# Control.net
KiCad netlist of a schematic drawn in Altium Designer
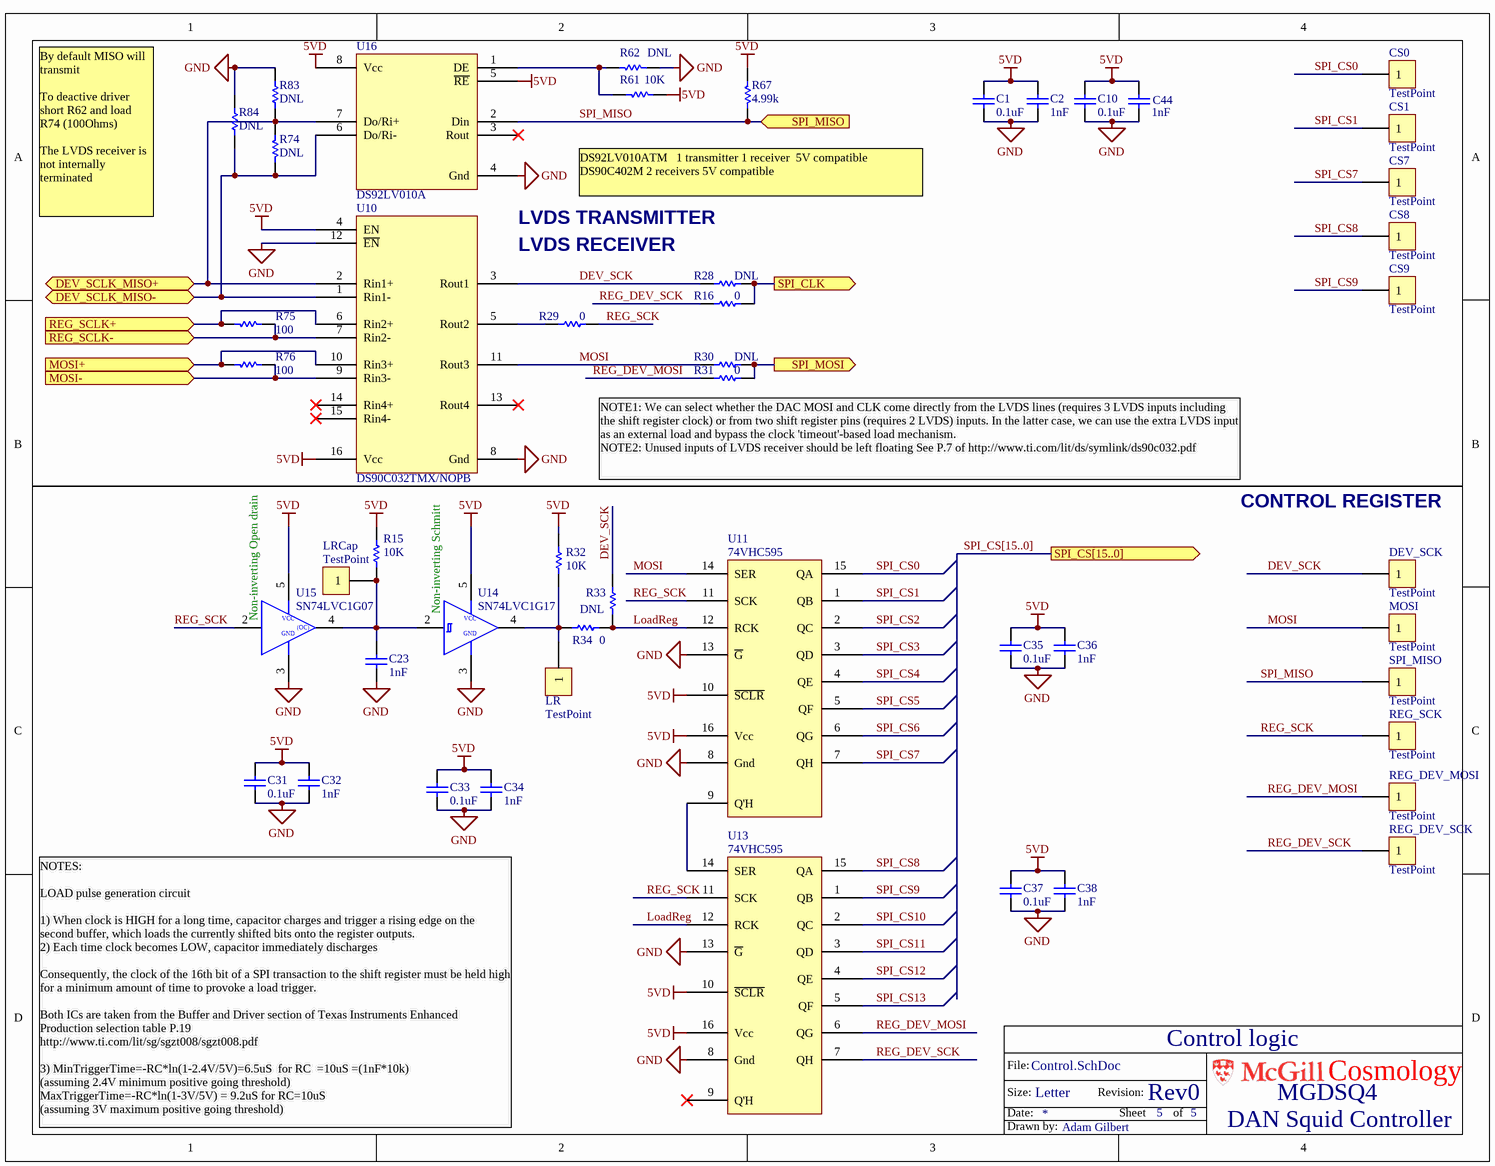
[diagram p0: Control.SchDoc]

(export (version "E")
  (design (tool "Eeschema 10.0.6"))
  (components
    (comp (ref "C1")
      (value "0.1uF")
      (footprint "0603")
      (description "Capacitor, Ceramic, 0603")
      (fields (field (name "MANUFACTURER") "Generic"))
      (libsource (lib "MiniSquidCtrl") (part "Cap0603"))
    )
    (comp (ref "C2")
      (value "1nF")
      (footprint "0603")
      (description "Capacitor, Ceramic, 0603")
      (fields (field (name "MANUFACTURER") "Generic"))
      (libsource (lib "MiniSquidCtrl") (part "Cap0603"))
    )
    (comp (ref "C10")
      (value "0.1uF")
      (footprint "0603")
      (description "Capacitor, Ceramic, 0603")
      (fields (field (name "MANUFACTURER") "Generic"))
      (libsource (lib "MiniSquidCtrl") (part "Cap0603"))
    )
    (comp (ref "C23")
      (value "1nF")
      (footprint "0603")
      (description "Capacitor, Ceramic, 0603")
      (fields (field (name "MANUFACTURER") "Generic"))
      (libsource (lib "MiniSquidCtrl") (part "Cap0603"))
    )
    (comp (ref "C31")
      (value "0.1uF")
      (footprint "0603")
      (description "Capacitor, Ceramic, 0603")
      (fields (field (name "MANUFACTURER") "Generic"))
      (libsource (lib "MiniSquidCtrl") (part "Cap0603"))
    )
    (comp (ref "C32")
      (value "1nF")
      (footprint "0603")
      (description "Capacitor, Ceramic, 0603")
      (fields (field (name "MANUFACTURER") "Generic"))
      (libsource (lib "MiniSquidCtrl") (part "Cap0603"))
    )
    (comp (ref "C33")
      (value "0.1uF")
      (footprint "0603")
      (description "Capacitor, Ceramic, 0603")
      (fields (field (name "MANUFACTURER") "Generic"))
      (libsource (lib "MiniSquidCtrl") (part "Cap0603"))
    )
    (comp (ref "C34")
      (value "1nF")
      (footprint "0603")
      (description "Capacitor, Ceramic, 0603")
      (fields (field (name "MANUFACTURER") "Generic"))
      (libsource (lib "MiniSquidCtrl") (part "Cap0603"))
    )
    (comp (ref "C35")
      (value "0.1uF")
      (footprint "0603")
      (description "Capacitor, Ceramic, 0603")
      (fields (field (name "MANUFACTURER") "Generic"))
      (libsource (lib "MiniSquidCtrl") (part "Cap0603"))
    )
    (comp (ref "C36")
      (value "1nF")
      (footprint "0603")
      (description "Capacitor, Ceramic, 0603")
      (fields (field (name "MANUFACTURER") "Generic"))
      (libsource (lib "MiniSquidCtrl") (part "Cap0603"))
    )
    (comp (ref "C37")
      (value "0.1uF")
      (footprint "0603")
      (description "Capacitor, Ceramic, 0603")
      (fields (field (name "MANUFACTURER") "Generic"))
      (libsource (lib "MiniSquidCtrl") (part "Cap0603"))
    )
    (comp (ref "C38")
      (value "1nF")
      (footprint "0603")
      (description "Capacitor, Ceramic, 0603")
      (fields (field (name "MANUFACTURER") "Generic"))
      (libsource (lib "MiniSquidCtrl") (part "Cap0603"))
    )
    (comp (ref "C44")
      (value "1nF")
      (footprint "0603")
      (description "Capacitor, Ceramic, 0603")
      (fields (field (name "MANUFACTURER") "Generic"))
      (libsource (lib "MiniSquidCtrl") (part "Cap0603"))
    )
    (comp (ref "CS0")
      (value "TestPoint")
      (footprint "TP-3520-SK")
      (description "TestPoint1")
      (libsource (lib "MiniSquidCtrl") (part "TestPoint"))
    )
    (comp (ref "CS1")
      (value "TestPoint")
      (footprint "TP-3520-SK")
      (description "TestPoint1")
      (libsource (lib "MiniSquidCtrl") (part "TestPoint"))
    )
    (comp (ref "CS7")
      (value "TestPoint")
      (footprint "TP-3520-SK")
      (description "TestPoint1")
      (libsource (lib "MiniSquidCtrl") (part "TestPoint"))
    )
    (comp (ref "CS8")
      (value "TestPoint")
      (footprint "TP-3520-SK")
      (description "TestPoint1")
      (libsource (lib "MiniSquidCtrl") (part "TestPoint"))
    )
    (comp (ref "CS9")
      (value "TestPoint")
      (footprint "TP-3520-SK")
      (description "TestPoint1")
      (libsource (lib "MiniSquidCtrl") (part "TestPoint"))
    )
    (comp (ref "DEV_SCK")
      (value "TestPoint")
      (footprint "TP-3520-SK")
      (description "TestPoint1")
      (libsource (lib "MiniSquidCtrl") (part "TestPoint"))
    )
    (comp (ref "LR")
      (value "TestPoint")
      (footprint "TP-3520-SK")
      (description "TestPoint1")
      (libsource (lib "") (part "TestPoint_2"))
    )
    (comp (ref "LRCap")
      (value "TestPoint")
      (footprint "TP-3520-SK")
      (description "TestPoint1")
      (libsource (lib "") (part "TestPoint_1"))
    )
    (comp (ref "MOSI")
      (value "TestPoint")
      (footprint "TP-3520-SK")
      (description "TestPoint1")
      (libsource (lib "MiniSquidCtrl") (part "TestPoint"))
    )
    (comp (ref "R15")
      (value "10K")
      (footprint "0603")
      (description "RES 0603")
      (fields (field (name "MANUFACTURER") "Generic") (field (name "Comment") "10k"))
      (libsource (lib "MiniSquidCtrl") (part "RES 0603"))
    )
    (comp (ref "R16")
      (value "0")
      (footprint "0603")
      (description "RES 0603")
      (fields (field (name "MANUFACTURER") "Generic"))
      (libsource (lib "MiniSquidCtrl") (part "RES 0603"))
    )
    (comp (ref "R28")
      (value "DNL")
      (footprint "0603")
      (description "Resistor")
      (fields (field (name "TOLERANCE") "1%") (field (name "POWER") "1/10W"))
      (libsource (lib "MiniSquidCtrl") (part "RES 0603"))
    )
    (comp (ref "R29")
      (value "0")
      (footprint "0603")
      (description "RES 0603")
      (fields (field (name "MANUFACTURER") "Generic"))
      (libsource (lib "MiniSquidCtrl") (part "RES 0603"))
    )
    (comp (ref "R30")
      (value "DNL")
      (footprint "0603")
      (description "Resistor")
      (fields (field (name "TOLERANCE") "1%") (field (name "POWER") "1/10W"))
      (libsource (lib "MiniSquidCtrl") (part "RES 0603"))
    )
    (comp (ref "R31")
      (value "0")
      (footprint "0603")
      (description "RES 0603")
      (fields (field (name "MANUFACTURER") "Generic"))
      (libsource (lib "MiniSquidCtrl") (part "RES 0603"))
    )
    (comp (ref "R32")
      (value "10K")
      (footprint "0603")
      (description "RES 0603")
      (fields (field (name "MANUFACTURER") "Generic") (field (name "Comment") "10k"))
      (libsource (lib "MiniSquidCtrl") (part "RES 0603"))
    )
    (comp (ref "R33")
      (value "DNL")
      (footprint "0603")
      (description "Resistor")
      (fields (field (name "TOLERANCE") "1%") (field (name "POWER") "1/10W"))
      (libsource (lib "MiniSquidCtrl") (part "RES 0603"))
    )
    (comp (ref "R34")
      (value "0")
      (footprint "0603")
      (description "RES 0603")
      (fields (field (name "MANUFACTURER") "Generic"))
      (libsource (lib "MiniSquidCtrl") (part "RES 0603"))
    )
    (comp (ref "R61")
      (value "10K")
      (footprint "0603")
      (description "RES 0603")
      (fields (field (name "MANUFACTURER") "Generic") (field (name "Comment") "10k"))
      (libsource (lib "MiniSquidCtrl") (part "RES 0603"))
    )
    (comp (ref "R62")
      (value "DNL")
      (footprint "0603")
      (description "RES 0603")
      (fields (field (name "MANUFACTURER") "Generic"))
      (libsource (lib "MiniSquidCtrl") (part "RES 0603"))
    )
    (comp (ref "R67")
      (value "4.99k")
      (footprint "0603")
      (description "RES 0603")
      (fields (field (name "MANUFACTURER") "Generic"))
      (libsource (lib "MiniSquidCtrl") (part "Res0603"))
    )
    (comp (ref "R74")
      (value "DNL")
      (footprint "0603")
      (description "RES 0603")
      (fields (field (name "MANUFACTURER") "Generic"))
      (libsource (lib "MiniSquidCtrl") (part "RES 0603"))
    )
    (comp (ref "R75")
      (value "100")
      (footprint "0603")
      (description "RES 0603")
      (fields (field (name "MANUFACTURER") "Generic"))
      (libsource (lib "MiniSquidCtrl") (part "RES 0603"))
    )
    (comp (ref "R76")
      (value "100")
      (footprint "0603")
      (description "RES 0603")
      (fields (field (name "MANUFACTURER") "Generic"))
      (libsource (lib "MiniSquidCtrl") (part "RES 0603"))
    )
    (comp (ref "R83")
      (value "DNL")
      (footprint "0603")
      (description "RES 0603")
      (fields (field (name "MANUFACTURER") "Generic"))
      (libsource (lib "MiniSquidCtrl") (part "Res0603"))
    )
    (comp (ref "R84")
      (value "DNL")
      (footprint "0603")
      (description "RES 0603")
      (fields (field (name "MANUFACTURER") "Generic"))
      (libsource (lib "MiniSquidCtrl") (part "Res0603"))
    )
    (comp (ref "REG_DEV_MOSI")
      (value "TestPoint")
      (footprint "TP-3520-SK")
      (description "TestPoint1")
      (libsource (lib "MiniSquidCtrl") (part "TestPoint"))
    )
    (comp (ref "REG_DEV_SCK")
      (value "TestPoint")
      (footprint "TP-3520-SK")
      (description "TestPoint1")
      (libsource (lib "MiniSquidCtrl") (part "TestPoint"))
    )
    (comp (ref "REG_SCK")
      (value "TestPoint")
      (footprint "TP-3520-SK")
      (description "TestPoint1")
      (libsource (lib "MiniSquidCtrl") (part "TestPoint"))
    )
    (comp (ref "SPI_MISO")
      (value "TestPoint")
      (footprint "TP-3520-SK")
      (description "TestPoint1")
      (libsource (lib "MiniSquidCtrl") (part "TestPoint"))
    )
    (comp (ref "U10")
      (value "DS90C032TMX/NOPB")
      (footprint "SO16")
      (description "IC LINE RCVR LVDS QUAD 16-SOIC")
      (fields (field (name "MANUFACTURER") "National Semiconductor"))
      (libsource (lib "MiniSquidCtrl") (part "DS90C032TMX/NOPB"))
    )
    (comp (ref "U11")
      (value "74VHC595")
      (footprint "SO16")
      (description "IC SHIFT REGISTER 8BIT 16-SOIC")
      (fields (field (name "MANUFACTURER") "Fairchild Semiconductor"))
      (libsource (lib "MiniSquidCtrl") (part "74VHC595"))
    )
    (comp (ref "U13")
      (value "74VHC595")
      (footprint "SO16")
      (description "IC SHIFT REGISTER 8BIT 16-SOIC")
      (fields (field (name "MANUFACTURER") "Fairchild Semiconductor"))
      (libsource (lib "MiniSquidCtrl") (part "74VHC595"))
    )
    (comp (ref "U14")
      (value "SN74LVC1G17")
      (footprint "SOT23-5")
      (description "IC BUFFER SCHMIT TRIG SOT235")
      (fields (field (name "MANUFACTURER") "Texas Instruments"))
      (libsource (lib "MiniSquidCtrl") (part "74LVC1G17"))
    )
    (comp (ref "U15")
      (value "SN74LVC1G07")
      (footprint "SOT23-5")
      (description "Single  NON-INVERTING BUFFER, Open Drain")
      (fields (field (name "PARTNUMBER") "SN74LVC1G07DBVR") (field (name "MANUFACTURER") "Texas Instruments"))
      (libsource (lib "MiniSquidCtrl") (part "74LVC1G07"))
    )
    (comp (ref "U16")
      (value "DS92LV010A")
      (footprint "SO8")
      (description "IC TXRX BUS LVDS SINGLE 8-SOI")
      (fields (field (name "MANUFACTURER") "National Semiconductor"))
      (libsource (lib "MiniSquidCtrl") (part "DS92LV010A"))
    )
  )
  (nets
    (net (code "3") (name "/DEV_SCK") (class "Default")
      (node (ref "DEV_SCK") (pin "1") (pinfunction "1_1") (pintype "passive"))
      (node (ref "R28") (pin "2") (pinfunction "2_2") (pintype "passive"))
      (node (ref "R33") (pin "1") (pinfunction "1_1") (pintype "passive"))
      (node (ref "U10") (pin "3") (pinfunction "Rout1_3") (pintype "passive"))
    )
    (net (code "4") (name "/DEV_SCLK_MISO+") (class "Default")
      (node (ref "R74") (pin "2") (pinfunction "2_2") (pintype "passive"))
      (node (ref "R83") (pin "2") (pinfunction "2_2") (pintype "passive"))
      (node (ref "U10") (pin "2") (pinfunction "Rin1+_2") (pintype "passive"))
      (node (ref "U16") (pin "7") (pinfunction "Do/Ri+_7") (pintype "passive"))
    )
    (net (code "5") (name "/DEV_SCLK_MISO-") (class "Default")
      (node (ref "R74") (pin "1") (pinfunction "1_1") (pintype "passive"))
      (node (ref "R84") (pin "2") (pinfunction "2_2") (pintype "passive"))
      (node (ref "U10") (pin "1") (pinfunction "Rin1-_1") (pintype "passive"))
      (node (ref "U16") (pin "6") (pinfunction "Do/Ri-_6") (pintype "passive"))
    )
    (net (code "6") (name "/LoadReg") (class "Default")
      (node (ref "R33") (pin "2") (pinfunction "2_2") (pintype "passive"))
      (node (ref "R34") (pin "1") (pinfunction "1_1") (pintype "passive"))
      (node (ref "U11") (pin "12") (pinfunction "RCK_12") (pintype "passive"))
      (node (ref "U13") (pin "12") (pinfunction "RCK_12") (pintype "passive"))
    )
    (net (code "7") (name "/MOSI") (class "Default")
      (node (ref "MOSI") (pin "1") (pinfunction "1_1") (pintype "passive"))
      (node (ref "R30") (pin "2") (pinfunction "2_2") (pintype "passive"))
      (node (ref "U10") (pin "11") (pinfunction "Rout3_11") (pintype "passive"))
      (node (ref "U11") (pin "14") (pinfunction "SER_14") (pintype "passive"))
    )
    (net (code "8") (name "/MOSI+") (class "Default")
      (node (ref "R76") (pin "2") (pinfunction "2_2") (pintype "passive"))
      (node (ref "U10") (pin "10") (pinfunction "Rin3+_10") (pintype "passive"))
    )
    (net (code "9") (name "/MOSI-") (class "Default")
      (node (ref "R76") (pin "1") (pinfunction "1_1") (pintype "passive"))
      (node (ref "U10") (pin "9") (pinfunction "Rin3-_9") (pintype "passive"))
    )
    (net (code "10") (name "/REG_DEV_MOSI") (class "Default")
      (node (ref "R31") (pin "2") (pinfunction "2_2") (pintype "passive"))
      (node (ref "REG_DEV_MOSI") (pin "1") (pinfunction "1_1") (pintype "passive"))
      (node (ref "U13") (pin "6") (pinfunction "QG_6") (pintype "passive"))
    )
    (net (code "11") (name "/REG_DEV_SCK") (class "Default")
      (node (ref "R16") (pin "2") (pinfunction "2_2") (pintype "passive"))
      (node (ref "REG_DEV_SCK") (pin "1") (pinfunction "1_1") (pintype "passive"))
      (node (ref "U13") (pin "7") (pinfunction "QH_7") (pintype "passive"))
    )
    (net (code "12") (name "/REG_SCK") (class "Default")
      (node (ref "R29") (pin "1") (pinfunction "1_1") (pintype "passive"))
      (node (ref "REG_SCK") (pin "1") (pinfunction "1_1") (pintype "passive"))
      (node (ref "U11") (pin "11") (pinfunction "SCK_11") (pintype "passive"))
      (node (ref "U13") (pin "11") (pinfunction "SCK_11") (pintype "passive"))
      (node (ref "U15") (pin "2") (pinfunction "A_2") (pintype "passive"))
    )
    (net (code "13") (name "/REG_SCLK+") (class "Default")
      (node (ref "R75") (pin "2") (pinfunction "2_2") (pintype "passive"))
      (node (ref "U10") (pin "6") (pinfunction "Rin2+_6") (pintype "passive"))
    )
    (net (code "14") (name "/REG_SCLK-") (class "Default")
      (node (ref "R75") (pin "1") (pinfunction "1_1") (pintype "passive"))
      (node (ref "U10") (pin "7") (pinfunction "Rin2-_7") (pintype "passive"))
    )
    (net (code "15") (name "/SPI_CLK") (class "Default")
      (node (ref "R16") (pin "1") (pinfunction "1_1") (pintype "passive"))
      (node (ref "R28") (pin "1") (pinfunction "1_1") (pintype "passive"))
    )
    (net (code "16") (name "/SPI_CS0") (class "Default")
      (node (ref "CS0") (pin "1") (pinfunction "1_1") (pintype "passive"))
      (node (ref "U11") (pin "15") (pinfunction "QA_15") (pintype "passive"))
    )
    (net (code "17") (name "/SPI_CS1") (class "Default")
      (node (ref "CS1") (pin "1") (pinfunction "1_1") (pintype "passive"))
      (node (ref "U11") (pin "1") (pinfunction "QB_1") (pintype "passive"))
    )
    (net (code "18") (name "/SPI_CS2") (class "Default")
      (node (ref "U11") (pin "2") (pinfunction "QC_2") (pintype "passive"))
    )
    (net (code "19") (name "/SPI_CS3") (class "Default")
      (node (ref "U11") (pin "3") (pinfunction "QD_3") (pintype "passive"))
    )
    (net (code "20") (name "/SPI_CS4") (class "Default")
      (node (ref "U11") (pin "4") (pinfunction "QE_4") (pintype "passive"))
    )
    (net (code "21") (name "/SPI_CS5") (class "Default")
      (node (ref "U11") (pin "5") (pinfunction "QF_5") (pintype "passive"))
    )
    (net (code "22") (name "/SPI_CS6") (class "Default")
      (node (ref "U11") (pin "6") (pinfunction "QG_6") (pintype "passive"))
    )
    (net (code "23") (name "/SPI_CS7") (class "Default")
      (node (ref "CS7") (pin "1") (pinfunction "1_1") (pintype "passive"))
      (node (ref "U11") (pin "7") (pinfunction "QH_7") (pintype "passive"))
    )
    (net (code "24") (name "/SPI_CS8") (class "Default")
      (node (ref "CS8") (pin "1") (pinfunction "1_1") (pintype "passive"))
      (node (ref "U13") (pin "15") (pinfunction "QA_15") (pintype "passive"))
    )
    (net (code "25") (name "/SPI_CS9") (class "Default")
      (node (ref "CS9") (pin "1") (pinfunction "1_1") (pintype "passive"))
      (node (ref "U13") (pin "1") (pinfunction "QB_1") (pintype "passive"))
    )
    (net (code "26") (name "/SPI_CS10") (class "Default")
      (node (ref "U13") (pin "2") (pinfunction "QC_2") (pintype "passive"))
    )
    (net (code "27") (name "/SPI_CS11") (class "Default")
      (node (ref "U13") (pin "3") (pinfunction "QD_3") (pintype "passive"))
    )
    (net (code "28") (name "/SPI_CS12") (class "Default")
      (node (ref "U13") (pin "4") (pinfunction "QE_4") (pintype "passive"))
    )
    (net (code "29") (name "/SPI_CS13") (class "Default")
      (node (ref "U13") (pin "5") (pinfunction "QF_5") (pintype "passive"))
    )
    (net (code "31") (name "/SPI_MISO") (class "Default")
      (node (ref "R67") (pin "1") (pinfunction "1_1") (pintype "passive"))
      (node (ref "SPI_MISO") (pin "1") (pinfunction "1_1") (pintype "passive"))
      (node (ref "U16") (pin "2") (pinfunction "Din_2") (pintype "passive"))
    )
    (net (code "32") (name "/SPI_MOSI") (class "Default")
      (node (ref "R30") (pin "1") (pinfunction "1_1") (pintype "passive"))
      (node (ref "R31") (pin "1") (pinfunction "1_1") (pintype "passive"))
    )
    (net (code "33") (name "5VD") (class "Default")
      (node (ref "C1") (pin "2") (pinfunction "2_2") (pintype "passive"))
      (node (ref "C10") (pin "2") (pinfunction "2_2") (pintype "passive"))
      (node (ref "C2") (pin "2") (pinfunction "2_2") (pintype "passive"))
      (node (ref "C31") (pin "2") (pinfunction "2_2") (pintype "passive"))
      (node (ref "C32") (pin "2") (pinfunction "2_2") (pintype "passive"))
      (node (ref "C33") (pin "2") (pinfunction "2_2") (pintype "passive"))
      (node (ref "C34") (pin "2") (pinfunction "2_2") (pintype "passive"))
      (node (ref "C35") (pin "2") (pinfunction "2_2") (pintype "passive"))
      (node (ref "C36") (pin "2") (pinfunction "2_2") (pintype "passive"))
      (node (ref "C37") (pin "2") (pinfunction "2_2") (pintype "passive"))
      (node (ref "C38") (pin "2") (pinfunction "2_2") (pintype "passive"))
      (node (ref "C44") (pin "2") (pinfunction "2_2") (pintype "passive"))
      (node (ref "R15") (pin "2") (pinfunction "2_2") (pintype "passive"))
      (node (ref "R32") (pin "2") (pinfunction "2_2") (pintype "passive"))
      (node (ref "R61") (pin "2") (pinfunction "2_2") (pintype "passive"))
      (node (ref "R67") (pin "2") (pinfunction "2_2") (pintype "passive"))
      (node (ref "U10") (pin "16") (pinfunction "Vcc_16") (pintype "passive"))
      (node (ref "U10") (pin "4") (pinfunction "EN_4") (pintype "passive"))
      (node (ref "U11") (pin "10") (pinfunction "~{SCLR}_10") (pintype "passive"))
      (node (ref "U11") (pin "16") (pinfunction "Vcc_16") (pintype "passive"))
      (node (ref "U13") (pin "10") (pinfunction "~{SCLR}_10") (pintype "passive"))
      (node (ref "U13") (pin "16") (pinfunction "Vcc_16") (pintype "passive"))
      (node (ref "U14") (pin "5") (pinfunction "Vcc_5") (pintype "power_in"))
      (node (ref "U15") (pin "5") (pinfunction "Vcc_5") (pintype "power_in"))
      (node (ref "U16") (pin "5") (pinfunction "~{RE}_5") (pintype "passive"))
      (node (ref "U16") (pin "8") (pinfunction "Vcc_8") (pintype "passive"))
    )
    (net (code "34") (name "GND") (class "Default")
      (node (ref "C1") (pin "1") (pinfunction "1_1") (pintype "passive"))
      (node (ref "C10") (pin "1") (pinfunction "1_1") (pintype "passive"))
      (node (ref "C2") (pin "1") (pinfunction "1_1") (pintype "passive"))
      (node (ref "C23") (pin "1") (pinfunction "1_1") (pintype "passive"))
      (node (ref "C31") (pin "1") (pinfunction "1_1") (pintype "passive"))
      (node (ref "C32") (pin "1") (pinfunction "1_1") (pintype "passive"))
      (node (ref "C33") (pin "1") (pinfunction "1_1") (pintype "passive"))
      (node (ref "C34") (pin "1") (pinfunction "1_1") (pintype "passive"))
      (node (ref "C35") (pin "1") (pinfunction "1_1") (pintype "passive"))
      (node (ref "C36") (pin "1") (pinfunction "1_1") (pintype "passive"))
      (node (ref "C37") (pin "1") (pinfunction "1_1") (pintype "passive"))
      (node (ref "C38") (pin "1") (pinfunction "1_1") (pintype "passive"))
      (node (ref "C44") (pin "1") (pinfunction "1_1") (pintype "passive"))
      (node (ref "R62") (pin "2") (pinfunction "2_2") (pintype "passive"))
      (node (ref "R83") (pin "1") (pinfunction "1_1") (pintype "passive"))
      (node (ref "R84") (pin "1") (pinfunction "1_1") (pintype "passive"))
      (node (ref "U10") (pin "12") (pinfunction "~{EN}_12") (pintype "passive"))
      (node (ref "U10") (pin "8") (pinfunction "Gnd_8") (pintype "passive"))
      (node (ref "U11") (pin "13") (pinfunction "~{G}_13") (pintype "passive"))
      (node (ref "U11") (pin "8") (pinfunction "Gnd_8") (pintype "passive"))
      (node (ref "U13") (pin "13") (pinfunction "~{G}_13") (pintype "passive"))
      (node (ref "U13") (pin "8") (pinfunction "Gnd_8") (pintype "passive"))
      (node (ref "U14") (pin "3") (pinfunction "Gnd_3") (pintype "power_in"))
      (node (ref "U15") (pin "3") (pinfunction "Gnd_3") (pintype "power_in"))
      (node (ref "U16") (pin "4") (pinfunction "Gnd_4") (pintype "passive"))
    )
    (net (code "35") (name "Net-(U10-Rout2)") (class "Default")
      (node (ref "R29") (pin "2") (pinfunction "2_2") (pintype "passive"))
      (node (ref "U10") (pin "5") (pinfunction "Rout2_5") (pintype "passive"))
    )
    (net (code "36") (name "Net-(U11-Q'H)") (class "Default")
      (node (ref "U11") (pin "9") (pinfunction "Q'H_9") (pintype "passive"))
      (node (ref "U13") (pin "14") (pinfunction "SER_14") (pintype "passive"))
    )
    (net (code "37") (name "Net-(U14-A)") (class "Default")
      (node (ref "C23") (pin "2") (pinfunction "2_2") (pintype "passive"))
      (node (ref "LRCap") (pin "1") (pinfunction "1_1") (pintype "passive"))
      (node (ref "R15") (pin "1") (pinfunction "1_1") (pintype "passive"))
      (node (ref "U14") (pin "2") (pinfunction "A_2") (pintype "passive"))
      (node (ref "U15") (pin "4") (pinfunction "Y_4") (pintype "passive"))
    )
    (net (code "38") (name "Net-(U14-Y)") (class "Default")
      (node (ref "LR") (pin "1") (pinfunction "1_1") (pintype "passive"))
      (node (ref "R32") (pin "1") (pinfunction "1_1") (pintype "passive"))
      (node (ref "R34") (pin "2") (pinfunction "2_2") (pintype "passive"))
      (node (ref "U14") (pin "4") (pinfunction "Y_4") (pintype "passive"))
    )
    (net (code "39") (name "Net-(U16-DE)") (class "Default")
      (node (ref "R61") (pin "1") (pinfunction "1_1") (pintype "passive"))
      (node (ref "R62") (pin "1") (pinfunction "1_1") (pintype "passive"))
      (node (ref "U16") (pin "1") (pinfunction "DE_1") (pintype "passive"))
    )
    (net (code "40") (name "unconnected-(U10-Rin4+-Pad14)") (class "Default")
      (node (ref "U10") (pin "14") (pinfunction "Rin4+_14") (pintype "passive+no_connect"))
    )
    (net (code "41") (name "unconnected-(U10-Rin4--Pad15)") (class "Default")
      (node (ref "U10") (pin "15") (pinfunction "Rin4-_15") (pintype "passive+no_connect"))
    )
    (net (code "42") (name "unconnected-(U10-Rout4-Pad13)") (class "Default")
      (node (ref "U10") (pin "13") (pinfunction "Rout4_13") (pintype "passive+no_connect"))
    )
    (net (code "43") (name "unconnected-(U13-Q'H-Pad9)") (class "Default")
      (node (ref "U13") (pin "9") (pinfunction "Q'H_9") (pintype "passive+no_connect"))
    )
    (net (code "44") (name "unconnected-(U16-Rout-Pad3)") (class "Default")
      (node (ref "U16") (pin "3") (pinfunction "Rout_3") (pintype "passive+no_connect"))
    )
  )
)
